# schematic.net
KiCad netlist of a schematic drawn in Altium Designer
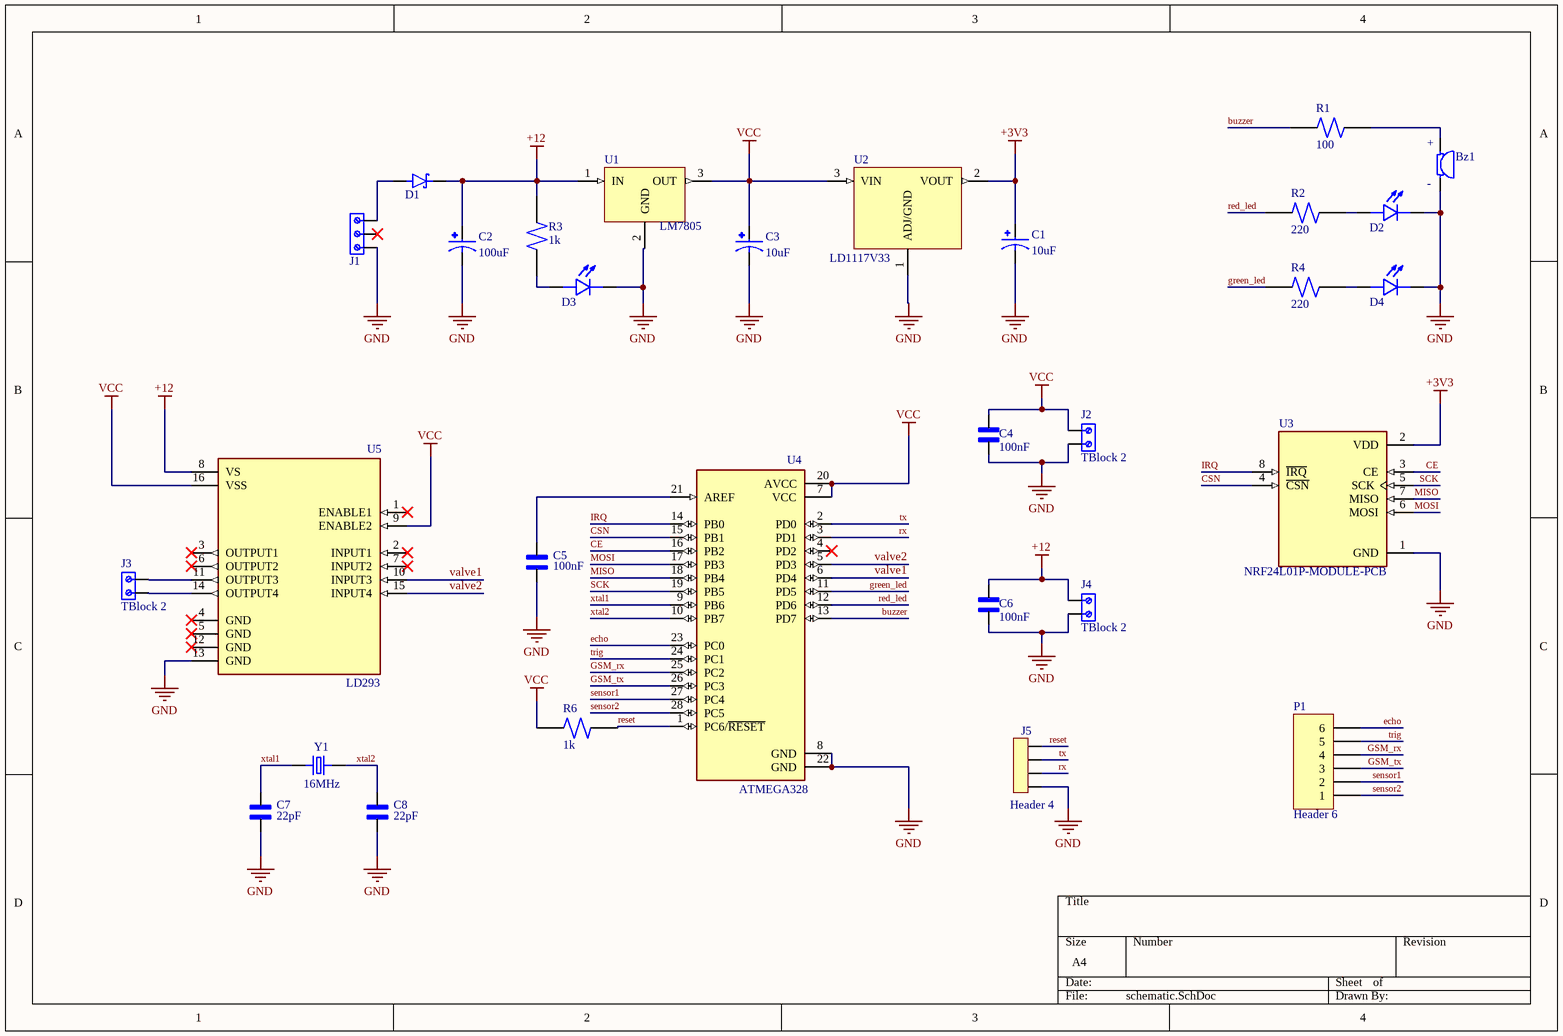
[diagram p0: schematic.SchDoc]

(export (version "E")
  (design (tool "Eeschema 10.0.6"))
  (components
    (comp (ref "Bz1")
      (value "AI-1223-TWT-12V-R")
      (footprint "XDCR_AI-1223-TWT-12V-R")
      (description "ELECTRO-MECHANICAL AUDIO INDICATOR")
      (fields (field (name "MF") "PUI Audio,"))
      (libsource (lib "Installed library") (part "Buzzer"))
    )
    (comp (ref "C1")
      (value "10uF")
      (footprint "CAPPRD500W50D500H1100")
      (description "FS-A")
      (fields (field (name "MF") "{'manufacturer': u'Panasonic'}") (field (name "MP") "EEUFS0J221B"))
      (libsource (lib "Installed library") (part "Electrolytic capacitor"))
    )
    (comp (ref "C2")
      (value "100uF")
      (footprint "CAPPRD500W50D500H1100")
      (description "FS-A")
      (fields (field (name "MF") "{'manufacturer': u'Panasonic'}") (field (name "MP") "EEUFS0J221B"))
      (libsource (lib "Installed library") (part "Electrolytic capacitor"))
    )
    (comp (ref "C3")
      (value "10uF")
      (footprint "CAPPRD500W50D500H1100")
      (description "FS-A")
      (fields (field (name "MF") "{'manufacturer': u'Panasonic'}") (field (name "MP") "EEUFS0J221B"))
      (libsource (lib "Installed library") (part "Electrolytic capacitor"))
    )
    (comp (ref "C4")
      (value "100nF")
      (footprint "CAPRB500W50L450T300H550")
      (description "2200 pF Â±10% 250V Ceramic Capacitor X7R Radial")
      (fields (field (name "DIGI-KEY_PART_NUMBER") "445-173386-1-ND") (field (name "MF") "TDK"))
      (libsource (lib "Installed library") (part "Ceramic capacitor"))
    )
    (comp (ref "C5")
      (value "100nF")
      (footprint "CAPRB500W50L450T300H550")
      (description "2200 pF Â±10% 250V Ceramic Capacitor X7R Radial")
      (fields (field (name "DIGI-KEY_PART_NUMBER") "445-173386-1-ND") (field (name "MF") "TDK"))
      (libsource (lib "") (part "Ceramic capacitor_1"))
    )
    (comp (ref "C6")
      (value "100nF")
      (footprint "CAPRB500W50L450T300H550")
      (description "2200 pF Â±10% 250V Ceramic Capacitor X7R Radial")
      (fields (field (name "DIGI-KEY_PART_NUMBER") "445-173386-1-ND") (field (name "MF") "TDK"))
      (libsource (lib "Installed library") (part "Ceramic capacitor"))
    )
    (comp (ref "C7")
      (value "22pF")
      (footprint "CAPRB500W50L450T300H550")
      (description "2200 pF Â±10% 250V Ceramic Capacitor X7R Radial")
      (fields (field (name "DIGI-KEY_PART_NUMBER") "445-173386-1-ND") (field (name "MF") "TDK"))
      (libsource (lib "") (part "Ceramic capacitor_1"))
    )
    (comp (ref "C8")
      (value "22pF")
      (footprint "CAPRB500W50L450T300H550")
      (description "2200 pF Â±10% 250V Ceramic Capacitor X7R Radial")
      (fields (field (name "DIGI-KEY_PART_NUMBER") "445-173386-1-ND") (field (name "MF") "TDK"))
      (libsource (lib "") (part "Ceramic capacitor_1"))
    )
    (comp (ref "D1")
      (value "1N5404")
      (footprint "DIOAD1990W125L900D530")
      (description "Diode Standard 400 V 3A Through Hole DO-201AD")
      (fields (field (name "MF") "ON Semiconductor"))
      (libsource (lib "Installed library") (part "Schrotic diode"))
    )
    (comp (ref "D2")
      (value "L08R5000Q1")
      (footprint "LEDRD254W57D500H1070")
      (description "LED, Orange, Through Hole, T-1 3/4 (5mm), 30 mA, 2.1 V, 635 nm")
      (fields (field (name "MF") "{'manufacturer': u'LED Technology'}"))
      (libsource (lib "Installed library") (part "LED"))
    )
    (comp (ref "D3")
      (value "L08R5000Q1")
      (footprint "LEDRD254W57D500H1070")
      (description "LED, Orange, Through Hole, T-1 3/4 (5mm), 30 mA, 2.1 V, 635 nm")
      (fields (field (name "MF") "{'manufacturer': u'LED Technology'}"))
      (libsource (lib "") (part "LED_1"))
    )
    (comp (ref "D4")
      (value "L08R5000Q1")
      (footprint "LEDRD254W57D500H1070")
      (description "LED, Orange, Through Hole, T-1 3/4 (5mm), 30 mA, 2.1 V, 635 nm")
      (fields (field (name "MF") "{'manufacturer': u'LED Technology'}"))
      (libsource (lib "Installed library") (part "LED"))
    )
    (comp (ref "J1")
      (value "691214110003")
      (footprint "691214110003")
      (description "3 Position Wire to Board Terminal Block Horizontal with Board 0.138 (3.50mm) Through Hole")
      (fields (field (name "MF") "Wurth Elektronik"))
      (libsource (lib "Installed library") (part "Terminal blocks - 3Pins (Small)"))
    )
    (comp (ref "J2")
      (value "TBlock 2")
      (footprint "691111710002")
      (description "2 Position Wire to Board Terminal Block Horizontal with Board 0.197 _5.00mm_ Through Hole")
      (fields (field (name "MP") "691111710002") (field (name "MF") "Wurth Electronics"))
      (libsource (lib "Installed library") (part "Terminal Block - 2Pins"))
    )
    (comp (ref "J3")
      (value "TBlock 2")
      (footprint "691111710002")
      (description "2 Position Wire to Board Terminal Block Horizontal with Board 0.197 _5.00mm_ Through Hole")
      (fields (field (name "MP") "691111710002") (field (name "MF") "Wurth Electronics"))
      (libsource (lib "Installed library") (part "Terminal Block - 2Pins"))
    )
    (comp (ref "J4")
      (value "TBlock 2")
      (footprint "691111710002")
      (description "2 Position Wire to Board Terminal Block Horizontal with Board 0.197 _5.00mm_ Through Hole")
      (fields (field (name "MP") "691111710002") (field (name "MF") "Wurth Electronics"))
      (libsource (lib "Installed library") (part "Terminal Block - 2Pins"))
    )
    (comp (ref "J5")
      (value "Header 4")
      (footprint "SULLINS_PPTC041LFBN-RC")
      (description "4 Position Header Connector Through Hole")
      (fields (field (name "MP") "PPTC041LFBN-RC") (field (name "MF") "Sullins Connector"))
      (libsource (lib "Installed library") (part "Female header - 4Pins"))
    )
    (comp (ref "P1")
      (value "Header 6")
      (footprint "HDR1X6")
      (description "Header, 6-Pin")
      (fields (field (name "PUBLISHER") "Altium Limited"))
      (libsource (lib "Miscellaneous Connectors") (part "Header 6"))
    )
    (comp (ref "R1")
      (value "100")
      (footprint "RESAD1100W55L680D260")
      (description "(MFR-25FBF52-10K) 10,2 kOhm bei 1% 0,25W, 1/4W Durchbohrlochwiderstand Axial Metal Film")
      (fields (field (name "DIGI-KEY_PART_NUMBER") "10.2KXBK-ND") (field (name "MF") "Yageo"))
      (libsource (lib "Installed library") (part "Resistor (0.25W)"))
    )
    (comp (ref "R2")
      (value "220")
      (footprint "RESAD1100W55L680D260")
      (description "(MFR-25FBF52-10K) 10,2 kOhm bei 1% 0,25W, 1/4W Durchbohrlochwiderstand Axial Metal Film")
      (fields (field (name "DIGI-KEY_PART_NUMBER") "10.2KXBK-ND") (field (name "MF") "Yageo"))
      (libsource (lib "Installed library") (part "Resistor (0.25W)"))
    )
    (comp (ref "R3")
      (value "1k")
      (footprint "RESAD1100W55L680D260")
      (description "(MFR-25FBF52-10K) 10,2 kOhm bei 1% 0,25W, 1/4W Durchbohrlochwiderstand Axial Metal Film")
      (fields (field (name "DIGI-KEY_PART_NUMBER") "10.2KXBK-ND") (field (name "MF") "Yageo"))
      (libsource (lib "Installed library") (part "Resistor (0.25W)"))
    )
    (comp (ref "R4")
      (value "220")
      (footprint "RESAD1100W55L680D260")
      (description "(MFR-25FBF52-10K) 10,2 kOhm bei 1% 0,25W, 1/4W Durchbohrlochwiderstand Axial Metal Film")
      (fields (field (name "DIGI-KEY_PART_NUMBER") "10.2KXBK-ND") (field (name "MF") "Yageo"))
      (libsource (lib "Installed library") (part "Resistor (0.25W)"))
    )
    (comp (ref "R6")
      (value "1k")
      (footprint "RESAD1100W55L680D260")
      (description "(MFR-25FBF52-10K) 10,2 kOhm bei 1% 0,25W, 1/4W Durchbohrlochwiderstand Axial Metal Film")
      (fields (field (name "DIGI-KEY_PART_NUMBER") "10.2KXBK-ND") (field (name "MF") "Yageo"))
      (libsource (lib "Installed library") (part "Resistor (0.25W)"))
    )
    (comp (ref "U1")
      (value "LM7805")
      (footprint "TO254P1054X470X1955-3")
      (fields (field (name "MP") "LM7805CT/NOPB"))
      (libsource (lib "Voltage regulator") (part "LM7805CT/NOPB"))
    )
    (comp (ref "U2")
      (value "LD1117V33")
      (footprint "TO255P1020X450X1968-3")
      (libsource (lib "Voltage regulator") (part "LD1117V33"))
    )
    (comp (ref "U3")
      (value "NRF24L01P-MODULE-PCB")
      (footprint "XCVR_NRF24L01P-MODULE-PCB")
      (description "- Transceiver For Use With nRF24L01+")
      (fields (field (name "MF") "Nordic Semiconductor"))
      (libsource (lib "Modules") (part "NRF24L01P-MODULE-PCB"))
    )
    (comp (ref "U4")
      (value "ATMEGA328")
      (footprint "DIP794W46P254L2967H457Q28B")
      (description "ATmega Series 20 MHz 32 KB Flash 2 KB SRAM 8-Bit Microcontroller - DIP-28")
      (fields (field (name "MP") "ATMEGA328P-PU"))
      (libsource (lib "Installed library") (part "ATMEGA328P-PU"))
    )
    (comp (ref "U5")
      (value "LD293")
      (footprint "DIP880W50P254L2000H510Q16")
      (description "4-Channel Motor Driver 24V 16-Pin Power PDIP Tube")
      (fields (field (name "MP") "L293D"))
      (libsource (lib "Installed library") (part "L293D"))
    )
    (comp (ref "Y1")
      (value "16MHz")
      (footprint "XTAL_ECS-160-20-4X")
      (description "CRYSTAL T/H")
      (fields (field (name "MF") "{'manufacturer': u'ECS Inc.'}") (field (name "MP") "ECS-160-S-4"))
      (libsource (lib "Installed library") (part "Crystal oscilator"))
    )
  )
  (nets
    (net (code "1") (name "+3V3") (class "Default")
      (node (ref "C1") (pin "P") (pinfunction "P_P") (pintype "passive"))
      (node (ref "U2") (pin "2") (pinfunction "VOUT_2") (pintype "output"))
      (node (ref "U3") (pin "2") (pinfunction "VDD_2") (pintype "power_in"))
    )
    (net (code "2") (name "+12") (class "Default")
      (node (ref "C2") (pin "P") (pinfunction "P_P") (pintype "passive"))
      (node (ref "C6") (pin "2") (pinfunction "2_2") (pintype "passive"))
      (node (ref "D1") (pin "C") (pinfunction "K_C") (pintype "passive"))
      (node (ref "J4") (pin "2") (pinfunction "2_2") (pintype "passive"))
      (node (ref "R3") (pin "2") (pinfunction "2_2") (pintype "passive"))
      (node (ref "U1") (pin "1") (pinfunction "IN_1") (pintype "input"))
      (node (ref "U5") (pin "8") (pinfunction "VS_8") (pintype "power_in"))
    )
    (net (code "3") (name "/CE") (class "Default")
      (node (ref "U3") (pin "3") (pinfunction "CE_3") (pintype "input"))
      (node (ref "U4") (pin "16") (pinfunction "PB2_16") (pintype "bidirectional"))
    )
    (net (code "4") (name "/CSN") (class "Default")
      (node (ref "U3") (pin "4") (pinfunction "~{CSN}_4") (pintype "input"))
      (node (ref "U4") (pin "15") (pinfunction "PB1_15") (pintype "bidirectional"))
    )
    (net (code "5") (name "/GSM_rx") (class "Default")
      (node (ref "P1") (pin "4") (pinfunction "4_4") (pintype "passive"))
      (node (ref "U4") (pin "25") (pinfunction "PC2_25") (pintype "bidirectional"))
    )
    (net (code "6") (name "/GSM_tx") (class "Default")
      (node (ref "P1") (pin "3") (pinfunction "3_3") (pintype "passive"))
      (node (ref "U4") (pin "26") (pinfunction "PC3_26") (pintype "bidirectional"))
    )
    (net (code "7") (name "/IRQ") (class "Default")
      (node (ref "U3") (pin "8") (pinfunction "~{IRQ}_8") (pintype "input"))
      (node (ref "U4") (pin "14") (pinfunction "PB0_14") (pintype "bidirectional"))
    )
    (net (code "8") (name "/MISO") (class "Default")
      (node (ref "U3") (pin "7") (pinfunction "MISO_7") (pintype "input"))
      (node (ref "U4") (pin "18") (pinfunction "PB4_18") (pintype "bidirectional"))
    )
    (net (code "9") (name "/MOSI") (class "Default")
      (node (ref "U3") (pin "6") (pinfunction "MOSI_6") (pintype "input"))
      (node (ref "U4") (pin "17") (pinfunction "PB3_17") (pintype "bidirectional"))
    )
    (net (code "10") (name "/SCK") (class "Default")
      (node (ref "U3") (pin "5") (pinfunction "SCK_5") (pintype "input"))
      (node (ref "U4") (pin "19") (pinfunction "PB5_19") (pintype "bidirectional"))
    )
    (net (code "11") (name "/buzzer") (class "Default")
      (node (ref "R1") (pin "2") (pinfunction "2_2") (pintype "passive"))
      (node (ref "U4") (pin "13") (pinfunction "PD7_13") (pintype "bidirectional"))
    )
    (net (code "12") (name "/echo") (class "Default")
      (node (ref "P1") (pin "6") (pinfunction "6_6") (pintype "passive"))
      (node (ref "U4") (pin "23") (pinfunction "PC0_23") (pintype "bidirectional"))
    )
    (net (code "13") (name "/green_led") (class "Default")
      (node (ref "R4") (pin "2") (pinfunction "2_2") (pintype "passive"))
      (node (ref "U4") (pin "11") (pinfunction "PD5_11") (pintype "bidirectional"))
    )
    (net (code "14") (name "/red_led") (class "Default")
      (node (ref "R2") (pin "2") (pinfunction "2_2") (pintype "passive"))
      (node (ref "U4") (pin "12") (pinfunction "PD6_12") (pintype "bidirectional"))
    )
    (net (code "15") (name "/reset") (class "Default")
      (node (ref "J5") (pin "1") (pinfunction "1_1") (pintype "passive"))
      (node (ref "R6") (pin "1") (pinfunction "1_1") (pintype "passive"))
      (node (ref "U4") (pin "1") (pinfunction "PC6/~{RESET}_1") (pintype "bidirectional"))
    )
    (net (code "16") (name "/rx") (class "Default")
      (node (ref "J5") (pin "3") (pinfunction "3_3") (pintype "passive"))
      (node (ref "U4") (pin "3") (pinfunction "PD1_3") (pintype "bidirectional"))
    )
    (net (code "17") (name "/sensor1") (class "Default")
      (node (ref "P1") (pin "2") (pinfunction "2_2") (pintype "passive"))
      (node (ref "U4") (pin "27") (pinfunction "PC4_27") (pintype "bidirectional"))
    )
    (net (code "18") (name "/sensor2") (class "Default")
      (node (ref "P1") (pin "1") (pinfunction "1_1") (pintype "passive"))
      (node (ref "U4") (pin "28") (pinfunction "PC5_28") (pintype "bidirectional"))
    )
    (net (code "19") (name "/trig") (class "Default")
      (node (ref "P1") (pin "5") (pinfunction "5_5") (pintype "passive"))
      (node (ref "U4") (pin "24") (pinfunction "PC1_24") (pintype "bidirectional"))
    )
    (net (code "20") (name "/tx") (class "Default")
      (node (ref "J5") (pin "2") (pinfunction "2_2") (pintype "passive"))
      (node (ref "U4") (pin "2") (pinfunction "PD0_2") (pintype "bidirectional"))
    )
    (net (code "21") (name "/valve1") (class "Default")
      (node (ref "U4") (pin "6") (pinfunction "PD4_6") (pintype "bidirectional"))
      (node (ref "U5") (pin "10") (pinfunction "INPUT3_10") (pintype "input"))
    )
    (net (code "22") (name "/valve2") (class "Default")
      (node (ref "U4") (pin "5") (pinfunction "PD3_5") (pintype "bidirectional"))
      (node (ref "U5") (pin "15") (pinfunction "INPUT4_15") (pintype "input"))
    )
    (net (code "23") (name "/xtal1") (class "Default")
      (node (ref "C7") (pin "2") (pinfunction "2_2") (pintype "passive"))
      (node (ref "U4") (pin "9") (pinfunction "PB6_9") (pintype "bidirectional"))
      (node (ref "Y1") (pin "1") (pinfunction "1_1") (pintype "passive"))
    )
    (net (code "24") (name "/xtal2") (class "Default")
      (node (ref "C8") (pin "2") (pinfunction "2_2") (pintype "passive"))
      (node (ref "U4") (pin "10") (pinfunction "PB7_10") (pintype "bidirectional"))
      (node (ref "Y1") (pin "2") (pinfunction "2_2") (pintype "passive"))
    )
    (net (code "25") (name "GND") (class "Default")
      (node (ref "Bz1") (pin "N") (pinfunction "NEG_N") (pintype "passive"))
      (node (ref "C1") (pin "N") (pinfunction "N_N") (pintype "passive"))
      (node (ref "C2") (pin "N") (pinfunction "N_N") (pintype "passive"))
      (node (ref "C3") (pin "N") (pinfunction "N_N") (pintype "passive"))
      (node (ref "C4") (pin "1") (pinfunction "1_1") (pintype "passive"))
      (node (ref "C5") (pin "1") (pinfunction "1_1") (pintype "passive"))
      (node (ref "C6") (pin "1") (pinfunction "1_1") (pintype "passive"))
      (node (ref "C7") (pin "1") (pinfunction "1_1") (pintype "passive"))
      (node (ref "C8") (pin "1") (pinfunction "1_1") (pintype "passive"))
      (node (ref "D2") (pin "C") (pinfunction "C_C") (pintype "passive"))
      (node (ref "D3") (pin "C") (pinfunction "C_C") (pintype "passive"))
      (node (ref "D4") (pin "C") (pinfunction "C_C") (pintype "passive"))
      (node (ref "J1") (pin "1") (pinfunction "1_1") (pintype "passive"))
      (node (ref "J2") (pin "1") (pinfunction "1_1") (pintype "passive"))
      (node (ref "J4") (pin "1") (pinfunction "1_1") (pintype "passive"))
      (node (ref "J5") (pin "4") (pinfunction "4_4") (pintype "passive"))
      (node (ref "U1") (pin "2") (pinfunction "GND_2") (pintype "power_in"))
      (node (ref "U2") (pin "1") (pinfunction "ADJ/GND_1") (pintype "passive"))
      (node (ref "U3") (pin "1") (pinfunction "GND_1") (pintype "power_in"))
      (node (ref "U4") (pin "22") (pinfunction "GND_22") (pintype "power_in"))
      (node (ref "U4") (pin "8") (pinfunction "GND_8") (pintype "power_in"))
      (node (ref "U5") (pin "13") (pinfunction "GND_13") (pintype "power_in"))
    )
    (net (code "26") (name "Net-(Bz1-POS)") (class "Default")
      (node (ref "Bz1") (pin "P") (pinfunction "POS_P") (pintype "passive"))
      (node (ref "R1") (pin "1") (pinfunction "1_1") (pintype "passive"))
    )
    (net (code "27") (name "Net-(D1-PadA)") (class "Default")
      (node (ref "D1") (pin "A") (pinfunction "A_A") (pintype "passive"))
      (node (ref "J1") (pin "3") (pinfunction "3_3") (pintype "passive"))
    )
    (net (code "28") (name "Net-(D2-PadA)") (class "Default")
      (node (ref "D2") (pin "A") (pinfunction "A_A") (pintype "passive"))
      (node (ref "R2") (pin "1") (pinfunction "1_1") (pintype "passive"))
    )
    (net (code "29") (name "Net-(D3-PadA)") (class "Default")
      (node (ref "D3") (pin "A") (pinfunction "A_A") (pintype "passive"))
      (node (ref "R3") (pin "1") (pinfunction "1_1") (pintype "passive"))
    )
    (net (code "30") (name "Net-(D4-PadA)") (class "Default")
      (node (ref "D4") (pin "A") (pinfunction "A_A") (pintype "passive"))
      (node (ref "R4") (pin "1") (pinfunction "1_1") (pintype "passive"))
    )
    (net (code "31") (name "Net-(U4-AREF)") (class "Default")
      (node (ref "C5") (pin "2") (pinfunction "2_2") (pintype "passive"))
      (node (ref "U4") (pin "21") (pinfunction "AREF_21") (pintype "input"))
    )
    (net (code "32") (name "Net-(U5-OUTPUT3)") (class "Default")
      (node (ref "J3") (pin "1") (pinfunction "1_1") (pintype "passive"))
      (node (ref "U5") (pin "11") (pinfunction "OUTPUT3_11") (pintype "output"))
    )
    (net (code "33") (name "Net-(U5-OUTPUT4)") (class "Default")
      (node (ref "J3") (pin "2") (pinfunction "2_2") (pintype "passive"))
      (node (ref "U5") (pin "14") (pinfunction "OUTPUT4_14") (pintype "output"))
    )
    (net (code "34") (name "VCC") (class "Default")
      (node (ref "C3") (pin "P") (pinfunction "P_P") (pintype "passive"))
      (node (ref "C4") (pin "2") (pinfunction "2_2") (pintype "passive"))
      (node (ref "J2") (pin "2") (pinfunction "2_2") (pintype "passive"))
      (node (ref "R6") (pin "2") (pinfunction "2_2") (pintype "passive"))
      (node (ref "U1") (pin "3") (pinfunction "OUT_3") (pintype "output"))
      (node (ref "U2") (pin "3") (pinfunction "VIN_3") (pintype "input"))
      (node (ref "U4") (pin "20") (pinfunction "AVCC_20") (pintype "power_in"))
      (node (ref "U4") (pin "7") (pinfunction "VCC_7") (pintype "power_in"))
      (node (ref "U5") (pin "16") (pinfunction "VSS_16") (pintype "power_in"))
      (node (ref "U5") (pin "9") (pinfunction "ENABLE2_9") (pintype "input"))
    )
    (net (code "35") (name "unconnected-(J1-Pad2)") (class "Default")
      (node (ref "J1") (pin "2") (pinfunction "2_2") (pintype "passive+no_connect"))
    )
    (net (code "36") (name "unconnected-(U4-PD2-Pad4)") (class "Default")
      (node (ref "U4") (pin "4") (pinfunction "PD2_4") (pintype "bidirectional+no_connect"))
    )
    (net (code "37") (name "unconnected-(U5-ENABLE1-Pad1)") (class "Default")
      (node (ref "U5") (pin "1") (pinfunction "ENABLE1_1") (pintype "input+no_connect"))
    )
    (net (code "38") (name "unconnected-(U5-GND-Pad4)") (class "Default")
      (node (ref "U5") (pin "4") (pinfunction "GND_4") (pintype "power_in+no_connect"))
    )
    (net (code "39") (name "unconnected-(U5-GND-Pad5)") (class "Default")
      (node (ref "U5") (pin "5") (pinfunction "GND_5") (pintype "power_in+no_connect"))
    )
    (net (code "40") (name "unconnected-(U5-GND-Pad12)") (class "Default")
      (node (ref "U5") (pin "12") (pinfunction "GND_12") (pintype "power_in+no_connect"))
    )
    (net (code "41") (name "unconnected-(U5-INPUT1-Pad2)") (class "Default")
      (node (ref "U5") (pin "2") (pinfunction "INPUT1_2") (pintype "input+no_connect"))
    )
    (net (code "42") (name "unconnected-(U5-INPUT2-Pad7)") (class "Default")
      (node (ref "U5") (pin "7") (pinfunction "INPUT2_7") (pintype "input+no_connect"))
    )
    (net (code "43") (name "unconnected-(U5-OUTPUT1-Pad3)") (class "Default")
      (node (ref "U5") (pin "3") (pinfunction "OUTPUT1_3") (pintype "output+no_connect"))
    )
    (net (code "44") (name "unconnected-(U5-OUTPUT2-Pad6)") (class "Default")
      (node (ref "U5") (pin "6") (pinfunction "OUTPUT2_6") (pintype "output+no_connect"))
    )
  )
)
